# Sensor_Module_0x09_0x10_Pulse_v1.net
KiCad netlist of a schematic drawn in EAGLE
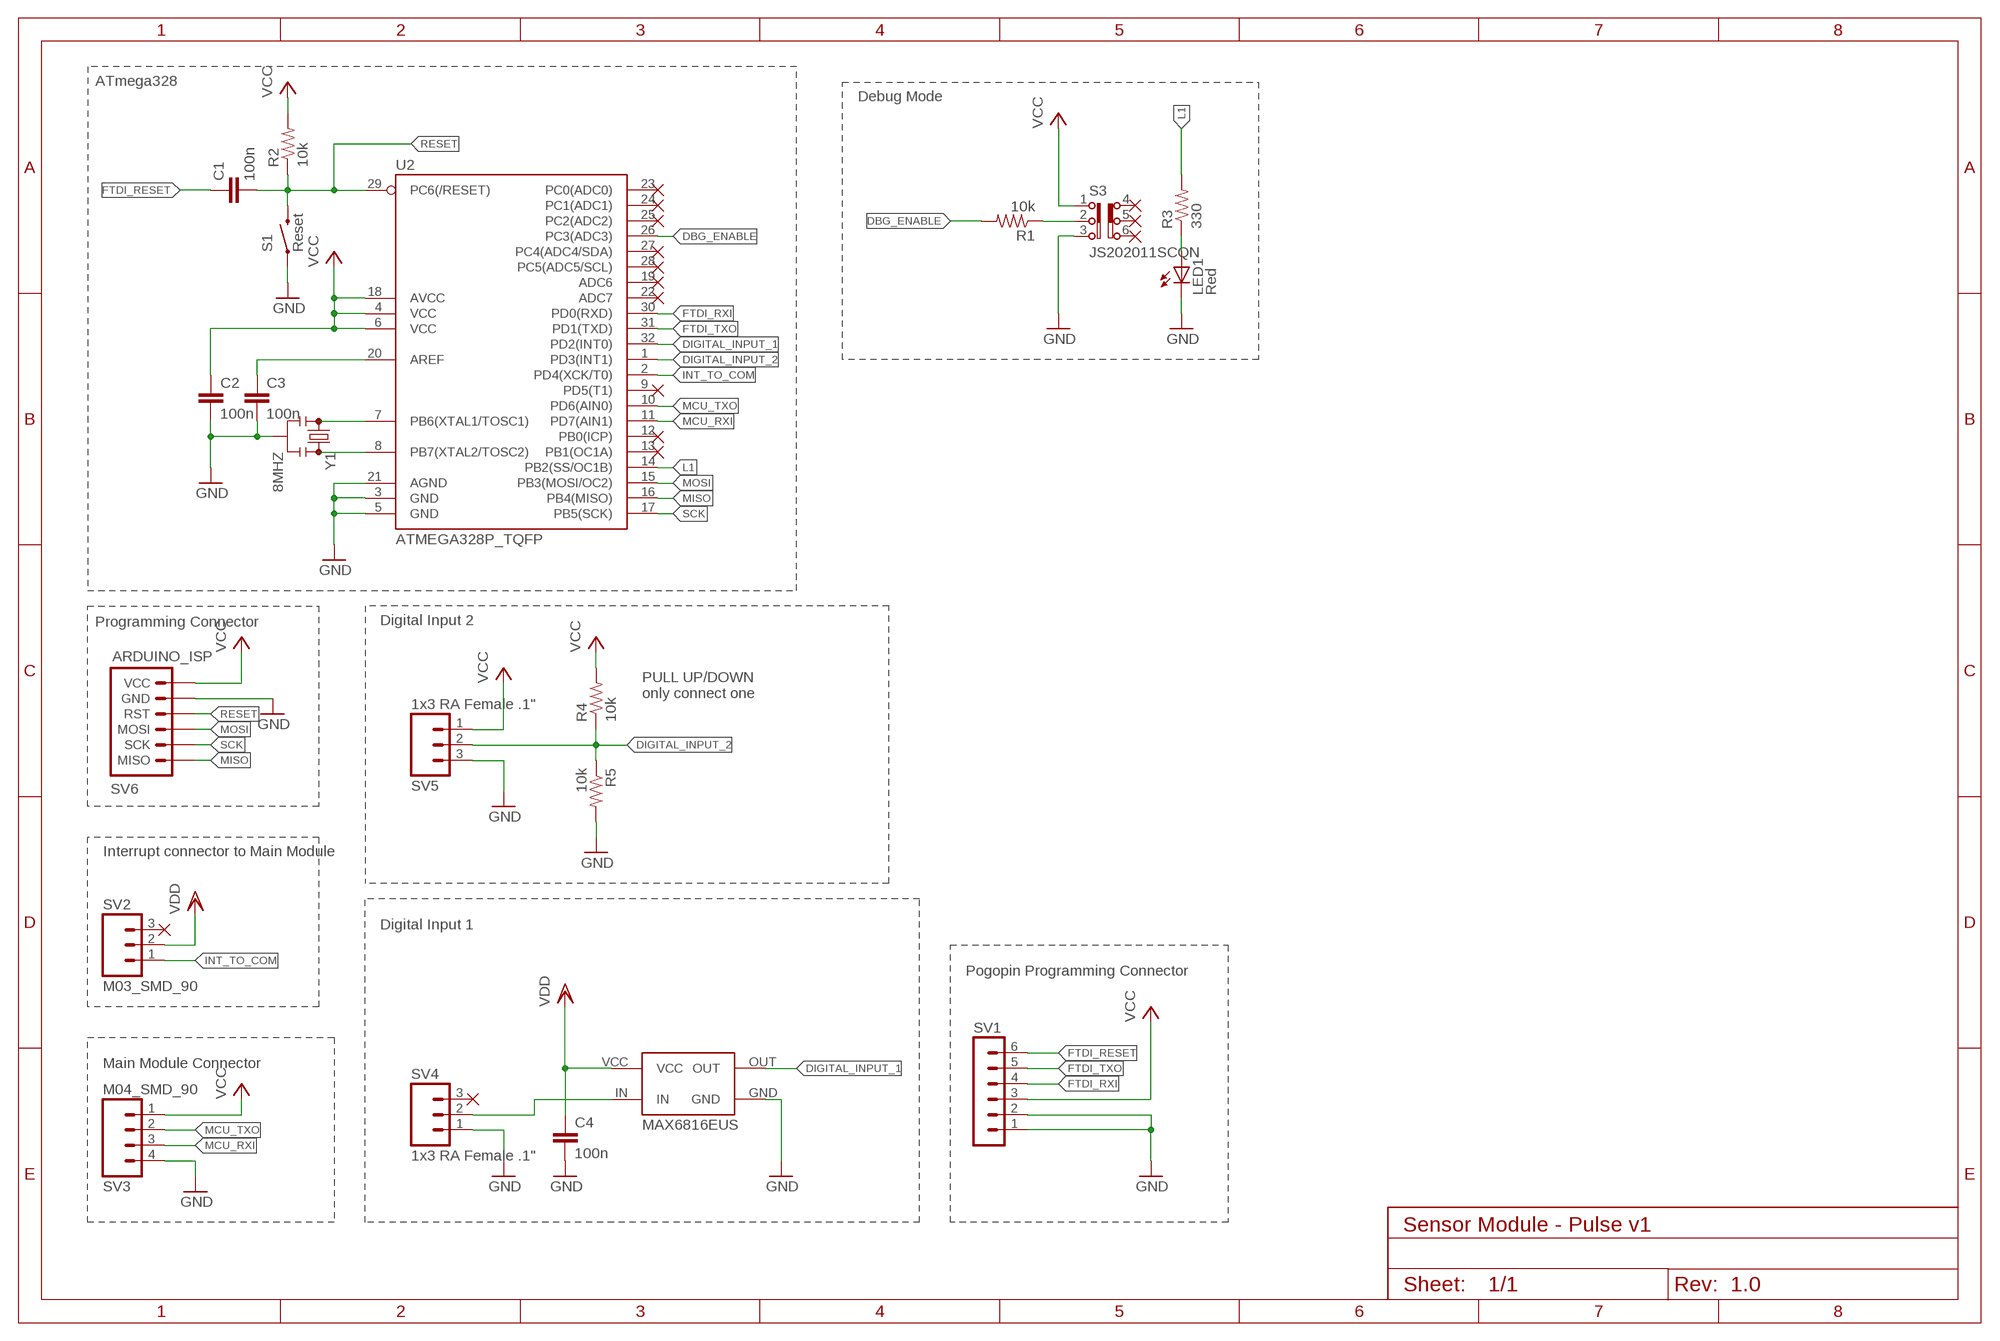
[diagram p0: schematic, sheet 1]

(export (version "E")
  (design (tool "Eeschema 10.0.6"))
  (components
    (comp (ref "C1")
      (value "100n")
      (footprint "eagle-import:C0805")
      (libsource (lib "eagle-import") (part "C"))
    )
    (comp (ref "C2")
      (value "100n")
      (footprint "eagle-import:C0805")
      (libsource (lib "eagle-import") (part "C"))
    )
    (comp (ref "C3")
      (value "100n")
      (footprint "eagle-import:C0805")
      (libsource (lib "eagle-import") (part "C"))
    )
    (comp (ref "C4")
      (value "100n")
      (footprint "eagle-import:C0805")
      (libsource (lib "eagle-import") (part "C"))
    )
    (comp (ref "LED1")
      (value "Red")
      (footprint "eagle-import:SML0805")
      (libsource (lib "eagle-import") (part "LEDSML0805"))
    )
    (comp (ref "R1")
      (value "10k")
      (footprint "eagle-import:0805")
      (libsource (lib "eagle-import") (part "RESISTOR0805-RES"))
    )
    (comp (ref "R2")
      (value "10k")
      (footprint "eagle-import:0805")
      (libsource (lib "eagle-import") (part "RESISTOR0805-RES"))
    )
    (comp (ref "R3")
      (value "330")
      (footprint "eagle-import:0805")
      (libsource (lib "eagle-import") (part "RESISTOR0805-RES"))
    )
    (comp (ref "R4")
      (value "10k")
      (footprint "eagle-import:0805")
      (libsource (lib "eagle-import") (part "RESISTOR0805-RES"))
    )
    (comp (ref "R5")
      (value "10k")
      (footprint "eagle-import:0805")
      (libsource (lib "eagle-import") (part "RESISTOR0805-RES"))
    )
    (comp (ref "S1")
      (value "Reset")
      (footprint "eagle-import:M-PUSHBUTTON-SMD")
      (libsource (lib "eagle-import") (part "PUSHBUTTON"))
    )
    (comp (ref "S3")
      (value "JS202011SCQN")
      (footprint "eagle-import:JS202011SCQN")
      (libsource (lib "eagle-import") (part "JS202011SCQN"))
    )
    (comp (ref "SV1")
      (value "MA06-1")
      (footprint "eagle-import:MA06-1")
      (libsource (lib "eagle-import") (part "MA06-1"))
    )
    (comp (ref "SV2")
      (value "M03_SMD_90")
      (footprint "eagle-import:M03_SMD_90")
      (libsource (lib "eagle-import") (part "M03_SMD_90"))
    )
    (comp (ref "SV3")
      (value "M04_SMD_90")
      (footprint "eagle-import:M04_SMD_90")
      (libsource (lib "eagle-import") (part "M04_SMD_90"))
    )
    (comp (ref "SV4")
      (value "1x3 RA Female .1\"")
      (footprint "eagle-import:1X03_SMD_RA_FEMALE")
      (libsource (lib "eagle-import") (part "M03SMD_RA_FEMALE"))
    )
    (comp (ref "SV5")
      (value "1x3 RA Female .1\"")
      (footprint "eagle-import:1X03_SMD_RA_FEMALE")
      (libsource (lib "eagle-import") (part "M03SMD_RA_FEMALE"))
    )
    (comp (ref "SV6")
      (value "ARDUINO_ISP")
      (footprint "eagle-import:M-2X3")
      (libsource (lib "eagle-import") (part "ARDUINO_ISP"))
    )
    (comp (ref "U$2")
      (value "MAX6816EUS")
      (footprint "eagle-import:SOT143")
      (libsource (lib "eagle-import") (part "MAX6816EUS"))
    )
    (comp (ref "U2")
      (value "ATMEGA328P_TQFP")
      (footprint "eagle-import:TQFP32-08")
      (libsource (lib "eagle-import") (part "ATMEGA328P_TQFP"))
    )
    (comp (ref "Y1")
      (value "8MHZ")
      (footprint "eagle-import:RESONATOR-SMD")
      (libsource (lib "eagle-import") (part "RESONATOR8MHZ"))
    )
  )
  (nets
    (net (code "1") (name "DBG_ENABLE") (class "Default")
      (node (ref "R1") (pin "2") (pinfunction "2_2") (pintype "passive"))
      (node (ref "U2") (pin "26") (pinfunction "PC3(ADC3)_26") (pintype "bidirectional"))
    )
    (net (code "2") (name "DIGITAL_INPUT_1") (class "Default")
      (node (ref "U$2") (pin "OUT") (pinfunction "OUT_OUT") (pintype "output"))
      (node (ref "U2") (pin "32") (pinfunction "PD2(INT0)_32") (pintype "bidirectional"))
    )
    (net (code "3") (name "DIGITAL_INPUT_2") (class "Default")
      (node (ref "R4") (pin "1") (pinfunction "1_1") (pintype "passive"))
      (node (ref "R5") (pin "1") (pinfunction "1_1") (pintype "passive"))
      (node (ref "SV5") (pin "2") (pinfunction "2_2") (pintype "passive"))
      (node (ref "U2") (pin "1") (pinfunction "PD3(INT1)_1") (pintype "bidirectional"))
    )
    (net (code "4") (name "FTDI_RESET") (class "Default")
      (node (ref "C1") (pin "1") (pinfunction "1_1") (pintype "passive"))
      (node (ref "SV1") (pin "6") (pinfunction "6_6") (pintype "passive"))
    )
    (net (code "5") (name "FTDI_RXI") (class "Default")
      (node (ref "SV1") (pin "4") (pinfunction "4_4") (pintype "passive"))
      (node (ref "U2") (pin "30") (pinfunction "PD0(RXD)_30") (pintype "bidirectional"))
    )
    (net (code "6") (name "FTDI_TXO") (class "Default")
      (node (ref "SV1") (pin "5") (pinfunction "5_5") (pintype "passive"))
      (node (ref "U2") (pin "31") (pinfunction "PD1(TXD)_31") (pintype "bidirectional"))
    )
    (net (code "7") (name "GND") (class "Default")
      (node (ref "C2") (pin "2") (pinfunction "2_2") (pintype "passive"))
      (node (ref "C3") (pin "2") (pinfunction "2_2") (pintype "passive"))
      (node (ref "C4") (pin "2") (pinfunction "2_2") (pintype "passive"))
      (node (ref "LED1") (pin "C") (pinfunction "C_C") (pintype "passive"))
      (node (ref "R5") (pin "2") (pinfunction "2_2") (pintype "passive"))
      (node (ref "S1") (pin "1") (pinfunction "LEFT_1") (pintype "passive"))
      (node (ref "S1") (pin "2") (pinfunction "LEFT_2") (pintype "passive"))
      (node (ref "S3") (pin "3") (pinfunction "3_3") (pintype "passive"))
      (node (ref "SV1") (pin "1") (pinfunction "1_1") (pintype "passive"))
      (node (ref "SV1") (pin "2") (pinfunction "2_2") (pintype "passive"))
      (node (ref "SV3") (pin "4") (pinfunction "4_4") (pintype "passive"))
      (node (ref "SV4") (pin "1") (pinfunction "1_1") (pintype "passive"))
      (node (ref "SV5") (pin "3") (pinfunction "3_3") (pintype "passive"))
      (node (ref "SV6") (pin "P$5") (pinfunction "GND_P$5") (pintype "passive"))
      (node (ref "U$2") (pin "GND") (pinfunction "GND_GND") (pintype "power_in"))
      (node (ref "U2") (pin "21") (pinfunction "AGND_21") (pintype "bidirectional"))
      (node (ref "U2") (pin "3") (pinfunction "GND_3") (pintype "bidirectional"))
      (node (ref "U2") (pin "5") (pinfunction "GND_5") (pintype "bidirectional"))
      (node (ref "Y1") (pin "2") (pinfunction "2_2") (pintype "passive"))
    )
    (net (code "8") (name "INT_TO_COM") (class "Default")
      (node (ref "SV2") (pin "1") (pinfunction "1_1") (pintype "passive"))
      (node (ref "U2") (pin "2") (pinfunction "PD4(XCK/T0)_2") (pintype "bidirectional"))
    )
    (net (code "9") (name "L1") (class "Default")
      (node (ref "R3") (pin "2") (pinfunction "2_2") (pintype "passive"))
      (node (ref "U2") (pin "14") (pinfunction "PB2(SS/OC1B)_14") (pintype "bidirectional"))
    )
    (net (code "10") (name "MCU_RXI") (class "Default")
      (node (ref "SV3") (pin "3") (pinfunction "3_3") (pintype "passive"))
      (node (ref "U2") (pin "11") (pinfunction "PD7(AIN1)_11") (pintype "bidirectional"))
    )
    (net (code "11") (name "MCU_TXO") (class "Default")
      (node (ref "SV3") (pin "2") (pinfunction "2_2") (pintype "passive"))
      (node (ref "U2") (pin "10") (pinfunction "PD6(AIN0)_10") (pintype "bidirectional"))
    )
    (net (code "12") (name "MISO") (class "Default")
      (node (ref "SV6") (pin "P$1") (pinfunction "MISO_P$1") (pintype "passive"))
      (node (ref "U2") (pin "16") (pinfunction "PB4(MISO)_16") (pintype "bidirectional"))
    )
    (net (code "13") (name "MOSI") (class "Default")
      (node (ref "SV6") (pin "P$3") (pinfunction "MOSI_P$3") (pintype "passive"))
      (node (ref "U2") (pin "15") (pinfunction "PB3(MOSI/OC2)_15") (pintype "bidirectional"))
    )
    (net (code "14") (name "Net-(LED1-PadA)") (class "Default")
      (node (ref "LED1") (pin "A") (pinfunction "A_A") (pintype "passive"))
      (node (ref "R3") (pin "1") (pinfunction "1_1") (pintype "passive"))
    )
    (net (code "15") (name "Net-(R1-Pad1)") (class "Default")
      (node (ref "R1") (pin "1") (pinfunction "1_1") (pintype "passive"))
      (node (ref "S3") (pin "2") (pinfunction "2_2") (pintype "passive"))
    )
    (net (code "16") (name "Net-(SV4-Pad2)") (class "Default")
      (node (ref "SV4") (pin "2") (pinfunction "2_2") (pintype "passive"))
      (node (ref "U$2") (pin "IN") (pinfunction "IN_IN") (pintype "input"))
    )
    (net (code "17") (name "Net-(U2-AREF)") (class "Default")
      (node (ref "C3") (pin "1") (pinfunction "1_1") (pintype "passive"))
      (node (ref "U2") (pin "20") (pinfunction "AREF_20") (pintype "bidirectional"))
    )
    (net (code "18") (name "Net-(U2-PB6(XTAL1{slash}TOSC1))") (class "Default")
      (node (ref "U2") (pin "7") (pinfunction "PB6(XTAL1/TOSC1)_7") (pintype "bidirectional"))
      (node (ref "Y1") (pin "1") (pinfunction "1_1") (pintype "passive"))
    )
    (net (code "19") (name "Net-(U2-PB7(XTAL2{slash}TOSC2))") (class "Default")
      (node (ref "U2") (pin "8") (pinfunction "PB7(XTAL2/TOSC2)_8") (pintype "bidirectional"))
      (node (ref "Y1") (pin "3") (pinfunction "3_3") (pintype "passive"))
    )
    (net (code "20") (name "RESET") (class "Default")
      (node (ref "C1") (pin "2") (pinfunction "2_2") (pintype "passive"))
      (node (ref "R2") (pin "1") (pinfunction "1_1") (pintype "passive"))
      (node (ref "S1") (pin "3") (pinfunction "RIGHT_3") (pintype "passive"))
      (node (ref "S1") (pin "4") (pinfunction "RIGHT_4") (pintype "passive"))
      (node (ref "SV6") (pin "P$4") (pinfunction "RST_P$4") (pintype "passive"))
      (node (ref "U2") (pin "29") (pinfunction "PC6(/RESET)_29") (pintype "bidirectional"))
    )
    (net (code "21") (name "SCK") (class "Default")
      (node (ref "SV6") (pin "P$2") (pinfunction "SCK_P$2") (pintype "passive"))
      (node (ref "U2") (pin "17") (pinfunction "PB5(SCK)_17") (pintype "bidirectional"))
    )
    (net (code "22") (name "VCC") (class "Default")
      (node (ref "C2") (pin "1") (pinfunction "1_1") (pintype "passive"))
      (node (ref "R2") (pin "2") (pinfunction "2_2") (pintype "passive"))
      (node (ref "R4") (pin "2") (pinfunction "2_2") (pintype "passive"))
      (node (ref "S3") (pin "1") (pinfunction "1_1") (pintype "passive"))
      (node (ref "SV1") (pin "3") (pinfunction "3_3") (pintype "passive"))
      (node (ref "SV3") (pin "1") (pinfunction "1_1") (pintype "passive"))
      (node (ref "SV5") (pin "1") (pinfunction "1_1") (pintype "passive"))
      (node (ref "SV6") (pin "P$6") (pinfunction "VCC_P$6") (pintype "passive"))
      (node (ref "U2") (pin "18") (pinfunction "AVCC_18") (pintype "bidirectional"))
      (node (ref "U2") (pin "4") (pinfunction "VCC_4") (pintype "bidirectional"))
      (node (ref "U2") (pin "6") (pinfunction "VCC_6") (pintype "bidirectional"))
    )
    (net (code "23") (name "VDD") (class "Default")
      (node (ref "C4") (pin "1") (pinfunction "1_1") (pintype "passive"))
      (node (ref "SV2") (pin "2") (pinfunction "2_2") (pintype "passive"))
      (node (ref "U$2") (pin "VCC") (pinfunction "VCC_VCC") (pintype "power_in"))
    )
    (net (code "24") (name "unconnected-(S3-Pad4)") (class "Default")
      (node (ref "S3") (pin "4") (pinfunction "4_4") (pintype "passive"))
    )
    (net (code "25") (name "unconnected-(S3-Pad5)") (class "Default")
      (node (ref "S3") (pin "5") (pinfunction "5_5") (pintype "passive"))
    )
    (net (code "26") (name "unconnected-(S3-Pad6)") (class "Default")
      (node (ref "S3") (pin "6") (pinfunction "6_6") (pintype "passive"))
    )
    (net (code "27") (name "unconnected-(SV2-Pad3)") (class "Default")
      (node (ref "SV2") (pin "3") (pinfunction "3_3") (pintype "passive"))
    )
    (net (code "28") (name "unconnected-(SV4-Pad3)") (class "Default")
      (node (ref "SV4") (pin "3") (pinfunction "3_3") (pintype "passive"))
    )
    (net (code "29") (name "unconnected-(U2-ADC6-Pad19)") (class "Default")
      (node (ref "U2") (pin "19") (pinfunction "ADC6_19") (pintype "bidirectional"))
    )
    (net (code "30") (name "unconnected-(U2-ADC7-Pad22)") (class "Default")
      (node (ref "U2") (pin "22") (pinfunction "ADC7_22") (pintype "bidirectional"))
    )
    (net (code "31") (name "unconnected-(U2-PB0(ICP)-Pad12)") (class "Default")
      (node (ref "U2") (pin "12") (pinfunction "PB0(ICP)_12") (pintype "bidirectional"))
    )
    (net (code "32") (name "unconnected-(U2-PB1(OC1A)-Pad13)") (class "Default")
      (node (ref "U2") (pin "13") (pinfunction "PB1(OC1A)_13") (pintype "bidirectional"))
    )
    (net (code "33") (name "unconnected-(U2-PC0(ADC0)-Pad23)") (class "Default")
      (node (ref "U2") (pin "23") (pinfunction "PC0(ADC0)_23") (pintype "bidirectional"))
    )
    (net (code "34") (name "unconnected-(U2-PC1(ADC1)-Pad24)") (class "Default")
      (node (ref "U2") (pin "24") (pinfunction "PC1(ADC1)_24") (pintype "bidirectional"))
    )
    (net (code "35") (name "unconnected-(U2-PC2(ADC2)-Pad25)") (class "Default")
      (node (ref "U2") (pin "25") (pinfunction "PC2(ADC2)_25") (pintype "bidirectional"))
    )
    (net (code "36") (name "unconnected-(U2-PC4(ADC4{slash}SDA)-Pad27)") (class "Default")
      (node (ref "U2") (pin "27") (pinfunction "PC4(ADC4/SDA)_27") (pintype "bidirectional"))
    )
    (net (code "37") (name "unconnected-(U2-PC5(ADC5{slash}SCL)-Pad28)") (class "Default")
      (node (ref "U2") (pin "28") (pinfunction "PC5(ADC5/SCL)_28") (pintype "bidirectional"))
    )
    (net (code "38") (name "unconnected-(U2-PD5(T1)-Pad9)") (class "Default")
      (node (ref "U2") (pin "9") (pinfunction "PD5(T1)_9") (pintype "bidirectional"))
    )
  )
)
